# Sensors.net
KiCad netlist of a schematic drawn in Altium Designer
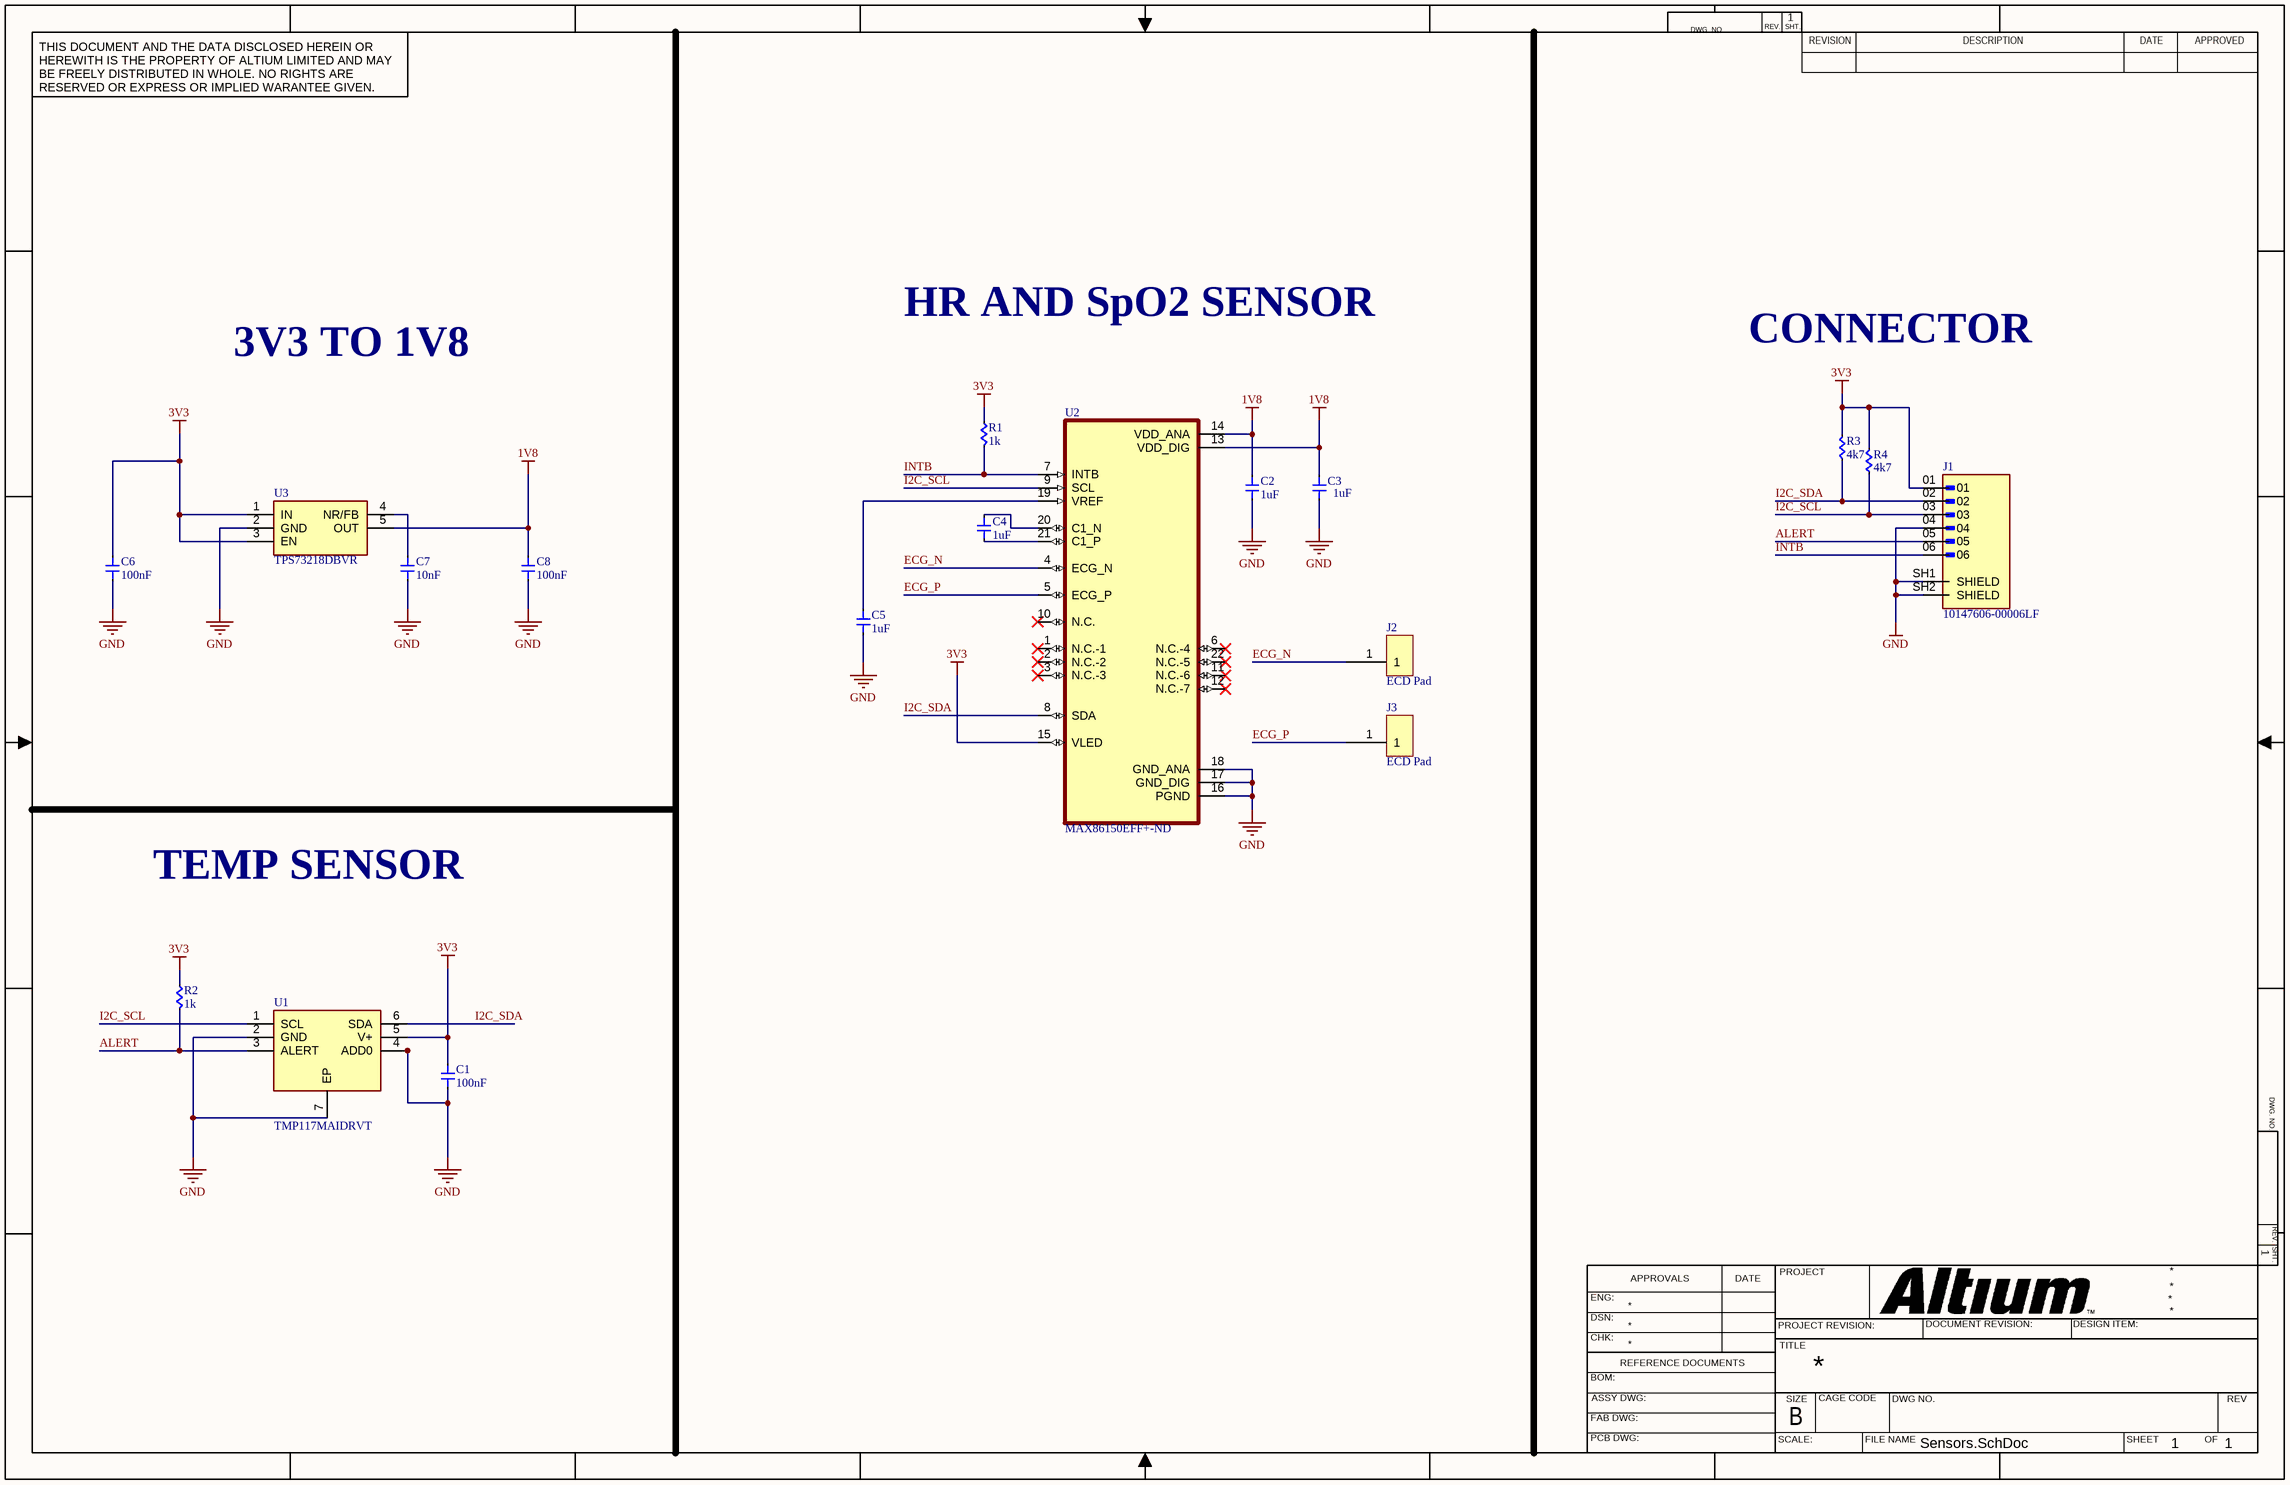
[diagram p0: Sensors.SchDoc]

(export (version "E")
  (design (tool "Eeschema 10.0.6"))
  (components
    (comp (ref "C1")
      (value "100nF")
      (footprint "Cap 0603")
      (description "Capacitor SMD 0603")
      (libsource (lib "Altium_Lib_by_KhueNguyenCreator") (part "Cap 0603"))
    )
    (comp (ref "C2")
      (value "1uF")
      (footprint "Cap 0603")
      (description "Capacitor SMD 0603")
      (libsource (lib "Altium_Lib_by_KhueNguyenCreator") (part "Cap 0603"))
    )
    (comp (ref "C3")
      (value "1uF")
      (footprint "Cap 0603")
      (description "Capacitor SMD 0603")
      (libsource (lib "Altium_Lib_by_KhueNguyenCreator") (part "Cap 0603"))
    )
    (comp (ref "C4")
      (value "1uF")
      (footprint "Cap 0603")
      (description "Capacitor SMD 0603")
      (libsource (lib "Altium_Lib_by_KhueNguyenCreator") (part "Cap 0603"))
    )
    (comp (ref "C5")
      (value "1uF")
      (footprint "Cap 0603")
      (description "Capacitor SMD 0603")
      (libsource (lib "Altium_Lib_by_KhueNguyenCreator") (part "Cap 0603"))
    )
    (comp (ref "C6")
      (value "100nF")
      (footprint "Cap 0603")
      (description "Capacitor SMD 0603")
      (libsource (lib "Altium_Lib_by_KhueNguyenCreator") (part "Cap 0603"))
    )
    (comp (ref "C7")
      (value "10nF")
      (footprint "Cap 0603")
      (description "Capacitor SMD 0603")
      (libsource (lib "Altium_Lib_by_KhueNguyenCreator") (part "Cap 0603"))
    )
    (comp (ref "C8")
      (value "100nF")
      (footprint "Cap 0603")
      (description "Capacitor SMD 0603")
      (libsource (lib "Altium_Lib_by_KhueNguyenCreator") (part "Cap 0603"))
    )
    (comp (ref "J1")
      (value "10147606-00006LF")
      (footprint "AMPHENOL_10147606-00006LF")
      (description "Minitek 1.0mm R/A SMT Header, 6 Positions, Tin Plating, Natural Color")
      (fields (field (name "MF") "Amphenol"))
      (libsource (lib "Sensors") (part "10147606-00006LF"))
    )
    (comp (ref "J2")
      (value "ECD Pad")
      (footprint "ECG Pad")
      (description "1cm x 1cm ECG Pad")
      (libsource (lib "Sensors") (part "ECG Pad"))
    )
    (comp (ref "J3")
      (value "ECD Pad")
      (footprint "ECG Pad")
      (description "1cm x 1cm ECG Pad")
      (libsource (lib "Sensors") (part "ECG Pad"))
    )
    (comp (ref "R1")
      (value "1k")
      (footprint "RES 0402")
      (description "RES SMD 0402")
      (fields
        (field (name "MANUFACTURER") "Vishay Dale")
        (field (name "MANUFACTURER PART NUMBER") "CRCW040210K0FKED")
      )
      (libsource (lib "Altium_Lib_by_KhueNguyenCreator") (part "RES 0402"))
    )
    (comp (ref "R2")
      (value "1k")
      (footprint "RES 0402")
      (description "RES SMD 0402")
      (fields
        (field (name "MANUFACTURER") "Vishay Dale")
        (field (name "MANUFACTURER PART NUMBER") "CRCW040210K0FKED")
      )
      (libsource (lib "Altium_Lib_by_KhueNguyenCreator") (part "RES 0402"))
    )
    (comp (ref "R3")
      (value "4k7")
      (footprint "RES 0603")
      (description "RES SMD 0603")
      (fields
        (field (name "MANUFACTURER") "Vishay Dale")
        (field (name "MANUFACTURER PART NUMBER") "CRCW040210K0FKED")
      )
      (libsource (lib "Altium_Lib_by_KhueNguyenCreator") (part "RES 0603"))
    )
    (comp (ref "R4")
      (value "4k7")
      (footprint "RES 0603")
      (description "RES SMD 0603")
      (fields
        (field (name "MANUFACTURER") "Vishay Dale")
        (field (name "MANUFACTURER PART NUMBER") "CRCW040210K0FKED")
      )
      (libsource (lib "Altium_Lib_by_KhueNguyenCreator") (part "RES 0603"))
    )
    (comp (ref "U1")
      (value "TMP117MAIDRVT")
      (footprint "SON65P200X200X80-7N")
      (description "Integrated Circuit")
      (fields (field (name "MOUSER PART NUMBER") "595-TMP117MAIDRVT"))
      (libsource (lib "Sensors") (part "TMP117MAIDRVT"))
    )
    (comp (ref "U2")
      (value "MAX86150EFF+-ND")
      (footprint "MAX86150EFF+")
      (description "SENSOR - OXIMETER/HEART RATE I2C")
      (fields (field (name "MF") "Analog Devices") (field (name "MP") "MAX86150EFF+"))
      (libsource (lib "Sensors") (part "MAX86150EFF+T"))
    )
    (comp (ref "U3")
      (value "TPS73218DBVR")
      (footprint "SOT95P280X145-5N")
      (description "Integrated Circuit")
      (fields (field (name "MOUSER PART NUMBER") "595-TPS73218DBVR"))
      (libsource (lib "Sensors") (part "TPS73218DBVR"))
    )
  )
  (nets
    (net (code "1") (name "/ALERT") (class "Default")
      (node (ref "J1") (pin "05") (pinfunction "05_05") (pintype "passive"))
      (node (ref "R2") (pin "2") (pinfunction "2_2") (pintype "passive"))
      (node (ref "U1") (pin "3") (pinfunction "ALERT_3") (pintype "passive"))
    )
    (net (code "2") (name "/ECG_N") (class "Default")
      (node (ref "J2") (pin "1") (pinfunction "1_1") (pintype "passive"))
      (node (ref "U2") (pin "4") (pinfunction "ECG_N_4") (pintype "bidirectional"))
    )
    (net (code "3") (name "/ECG_P") (class "Default")
      (node (ref "J3") (pin "1") (pinfunction "1_1") (pintype "passive"))
      (node (ref "U2") (pin "5") (pinfunction "ECG_P_5") (pintype "bidirectional"))
    )
    (net (code "4") (name "/I2C_SCL") (class "Default")
      (node (ref "J1") (pin "03") (pinfunction "03_03") (pintype "passive"))
      (node (ref "R4") (pin "1") (pinfunction "1_1") (pintype "passive"))
      (node (ref "U1") (pin "1") (pinfunction "SCL_1") (pintype "passive"))
      (node (ref "U2") (pin "9") (pinfunction "SCL_9") (pintype "input"))
    )
    (net (code "5") (name "/I2C_SDA") (class "Default")
      (node (ref "J1") (pin "02") (pinfunction "02_02") (pintype "passive"))
      (node (ref "R3") (pin "1") (pinfunction "1_1") (pintype "passive"))
      (node (ref "U1") (pin "6") (pinfunction "SDA_6") (pintype "passive"))
      (node (ref "U2") (pin "8") (pinfunction "SDA_8") (pintype "bidirectional"))
    )
    (net (code "6") (name "/INTB") (class "Default")
      (node (ref "J1") (pin "06") (pinfunction "06_06") (pintype "passive"))
      (node (ref "R1") (pin "2") (pinfunction "2_2") (pintype "passive"))
      (node (ref "U2") (pin "7") (pinfunction "INTB_7") (pintype "input"))
    )
    (net (code "7") (name "1V8") (class "Default")
      (node (ref "C2") (pin "1") (pinfunction "1_1") (pintype "passive"))
      (node (ref "C3") (pin "1") (pinfunction "1_1") (pintype "passive"))
      (node (ref "C8") (pin "1") (pinfunction "1_1") (pintype "passive"))
      (node (ref "U2") (pin "13") (pinfunction "VDD_DIG_13") (pintype "power_in"))
      (node (ref "U2") (pin "14") (pinfunction "VDD_ANA_14") (pintype "power_in"))
      (node (ref "U3") (pin "5") (pinfunction "OUT_5") (pintype "passive"))
    )
    (net (code "8") (name "3V3") (class "Default")
      (node (ref "C1") (pin "1") (pinfunction "1_1") (pintype "passive"))
      (node (ref "C6") (pin "1") (pinfunction "1_1") (pintype "passive"))
      (node (ref "J1") (pin "01") (pinfunction "01_01") (pintype "passive"))
      (node (ref "R1") (pin "1") (pinfunction "1_1") (pintype "passive"))
      (node (ref "R2") (pin "1") (pinfunction "1_1") (pintype "passive"))
      (node (ref "R3") (pin "2") (pinfunction "2_2") (pintype "passive"))
      (node (ref "R4") (pin "2") (pinfunction "2_2") (pintype "passive"))
      (node (ref "U1") (pin "5") (pinfunction "V+_5") (pintype "passive"))
      (node (ref "U2") (pin "15") (pinfunction "VLED_15") (pintype "bidirectional"))
      (node (ref "U3") (pin "1") (pinfunction "IN_1") (pintype "passive"))
      (node (ref "U3") (pin "3") (pinfunction "EN_3") (pintype "passive"))
    )
    (net (code "9") (name "GND") (class "Default")
      (node (ref "C1") (pin "2") (pinfunction "2_2") (pintype "passive"))
      (node (ref "C2") (pin "2") (pinfunction "2_2") (pintype "passive"))
      (node (ref "C3") (pin "2") (pinfunction "2_2") (pintype "passive"))
      (node (ref "C5") (pin "2") (pinfunction "2_2") (pintype "passive"))
      (node (ref "C6") (pin "2") (pinfunction "2_2") (pintype "passive"))
      (node (ref "C7") (pin "2") (pinfunction "2_2") (pintype "passive"))
      (node (ref "C8") (pin "2") (pinfunction "2_2") (pintype "passive"))
      (node (ref "J1") (pin "04") (pinfunction "04_04") (pintype "passive"))
      (node (ref "J1") (pin "SH1") (pinfunction "SHIELD_SH1") (pintype "passive"))
      (node (ref "J1") (pin "SH2") (pinfunction "SHIELD_SH2") (pintype "passive"))
      (node (ref "U1") (pin "2") (pinfunction "GND_2") (pintype "passive"))
      (node (ref "U1") (pin "4") (pinfunction "ADD0_4") (pintype "passive"))
      (node (ref "U1") (pin "7") (pinfunction "EP_7") (pintype "passive"))
      (node (ref "U2") (pin "16") (pinfunction "PGND_16") (pintype "power_in"))
      (node (ref "U2") (pin "17") (pinfunction "GND_DIG_17") (pintype "power_in"))
      (node (ref "U2") (pin "18") (pinfunction "GND_ANA_18") (pintype "power_in"))
      (node (ref "U3") (pin "2") (pinfunction "GND_2") (pintype "passive"))
    )
    (net (code "10") (name "Net-(U2-C1_N)") (class "Default")
      (node (ref "C4") (pin "1") (pinfunction "1_1") (pintype "passive"))
      (node (ref "U2") (pin "20") (pinfunction "C1_N_20") (pintype "bidirectional"))
    )
    (net (code "11") (name "Net-(U2-C1_P)") (class "Default")
      (node (ref "C4") (pin "2") (pinfunction "2_2") (pintype "passive"))
      (node (ref "U2") (pin "21") (pinfunction "C1_P_21") (pintype "bidirectional"))
    )
    (net (code "12") (name "Net-(U2-VREF)") (class "Default")
      (node (ref "C5") (pin "1") (pinfunction "1_1") (pintype "passive"))
      (node (ref "U2") (pin "19") (pinfunction "VREF_19") (pintype "input"))
    )
    (net (code "13") (name "Net-(U3-NR{slash}FB)") (class "Default")
      (node (ref "C7") (pin "1") (pinfunction "1_1") (pintype "passive"))
      (node (ref "U3") (pin "4") (pinfunction "NR/FB_4") (pintype "passive"))
    )
    (net (code "14") (name "unconnected-(U2-N.C.-1-Pad1)") (class "Default")
      (node (ref "U2") (pin "1") (pinfunction "N.C.-1_1") (pintype "bidirectional+no_connect"))
    )
    (net (code "15") (name "unconnected-(U2-N.C.-2-Pad2)") (class "Default")
      (node (ref "U2") (pin "2") (pinfunction "N.C.-2_2") (pintype "bidirectional+no_connect"))
    )
    (net (code "16") (name "unconnected-(U2-N.C.-3-Pad3)") (class "Default")
      (node (ref "U2") (pin "3") (pinfunction "N.C.-3_3") (pintype "bidirectional+no_connect"))
    )
    (net (code "17") (name "unconnected-(U2-N.C.-4-Pad6)") (class "Default")
      (node (ref "U2") (pin "6") (pinfunction "N.C.-4_6") (pintype "bidirectional+no_connect"))
    )
    (net (code "18") (name "unconnected-(U2-N.C.-5-Pad22)") (class "Default")
      (node (ref "U2") (pin "22") (pinfunction "N.C.-5_22") (pintype "bidirectional+no_connect"))
    )
    (net (code "19") (name "unconnected-(U2-N.C.-6-Pad11)") (class "Default")
      (node (ref "U2") (pin "11") (pinfunction "N.C.-6_11") (pintype "bidirectional+no_connect"))
    )
    (net (code "20") (name "unconnected-(U2-N.C.-7-Pad12)") (class "Default")
      (node (ref "U2") (pin "12") (pinfunction "N.C.-7_12") (pintype "bidirectional+no_connect"))
    )
    (net (code "21") (name "unconnected-(U2-N.C.-Pad10)") (class "Default")
      (node (ref "U2") (pin "10") (pinfunction "N.C._10") (pintype "bidirectional+no_connect"))
    )
  )
)
